# 6_SWITCHING.net
KiCad netlist of a schematic drawn in Altium Designer
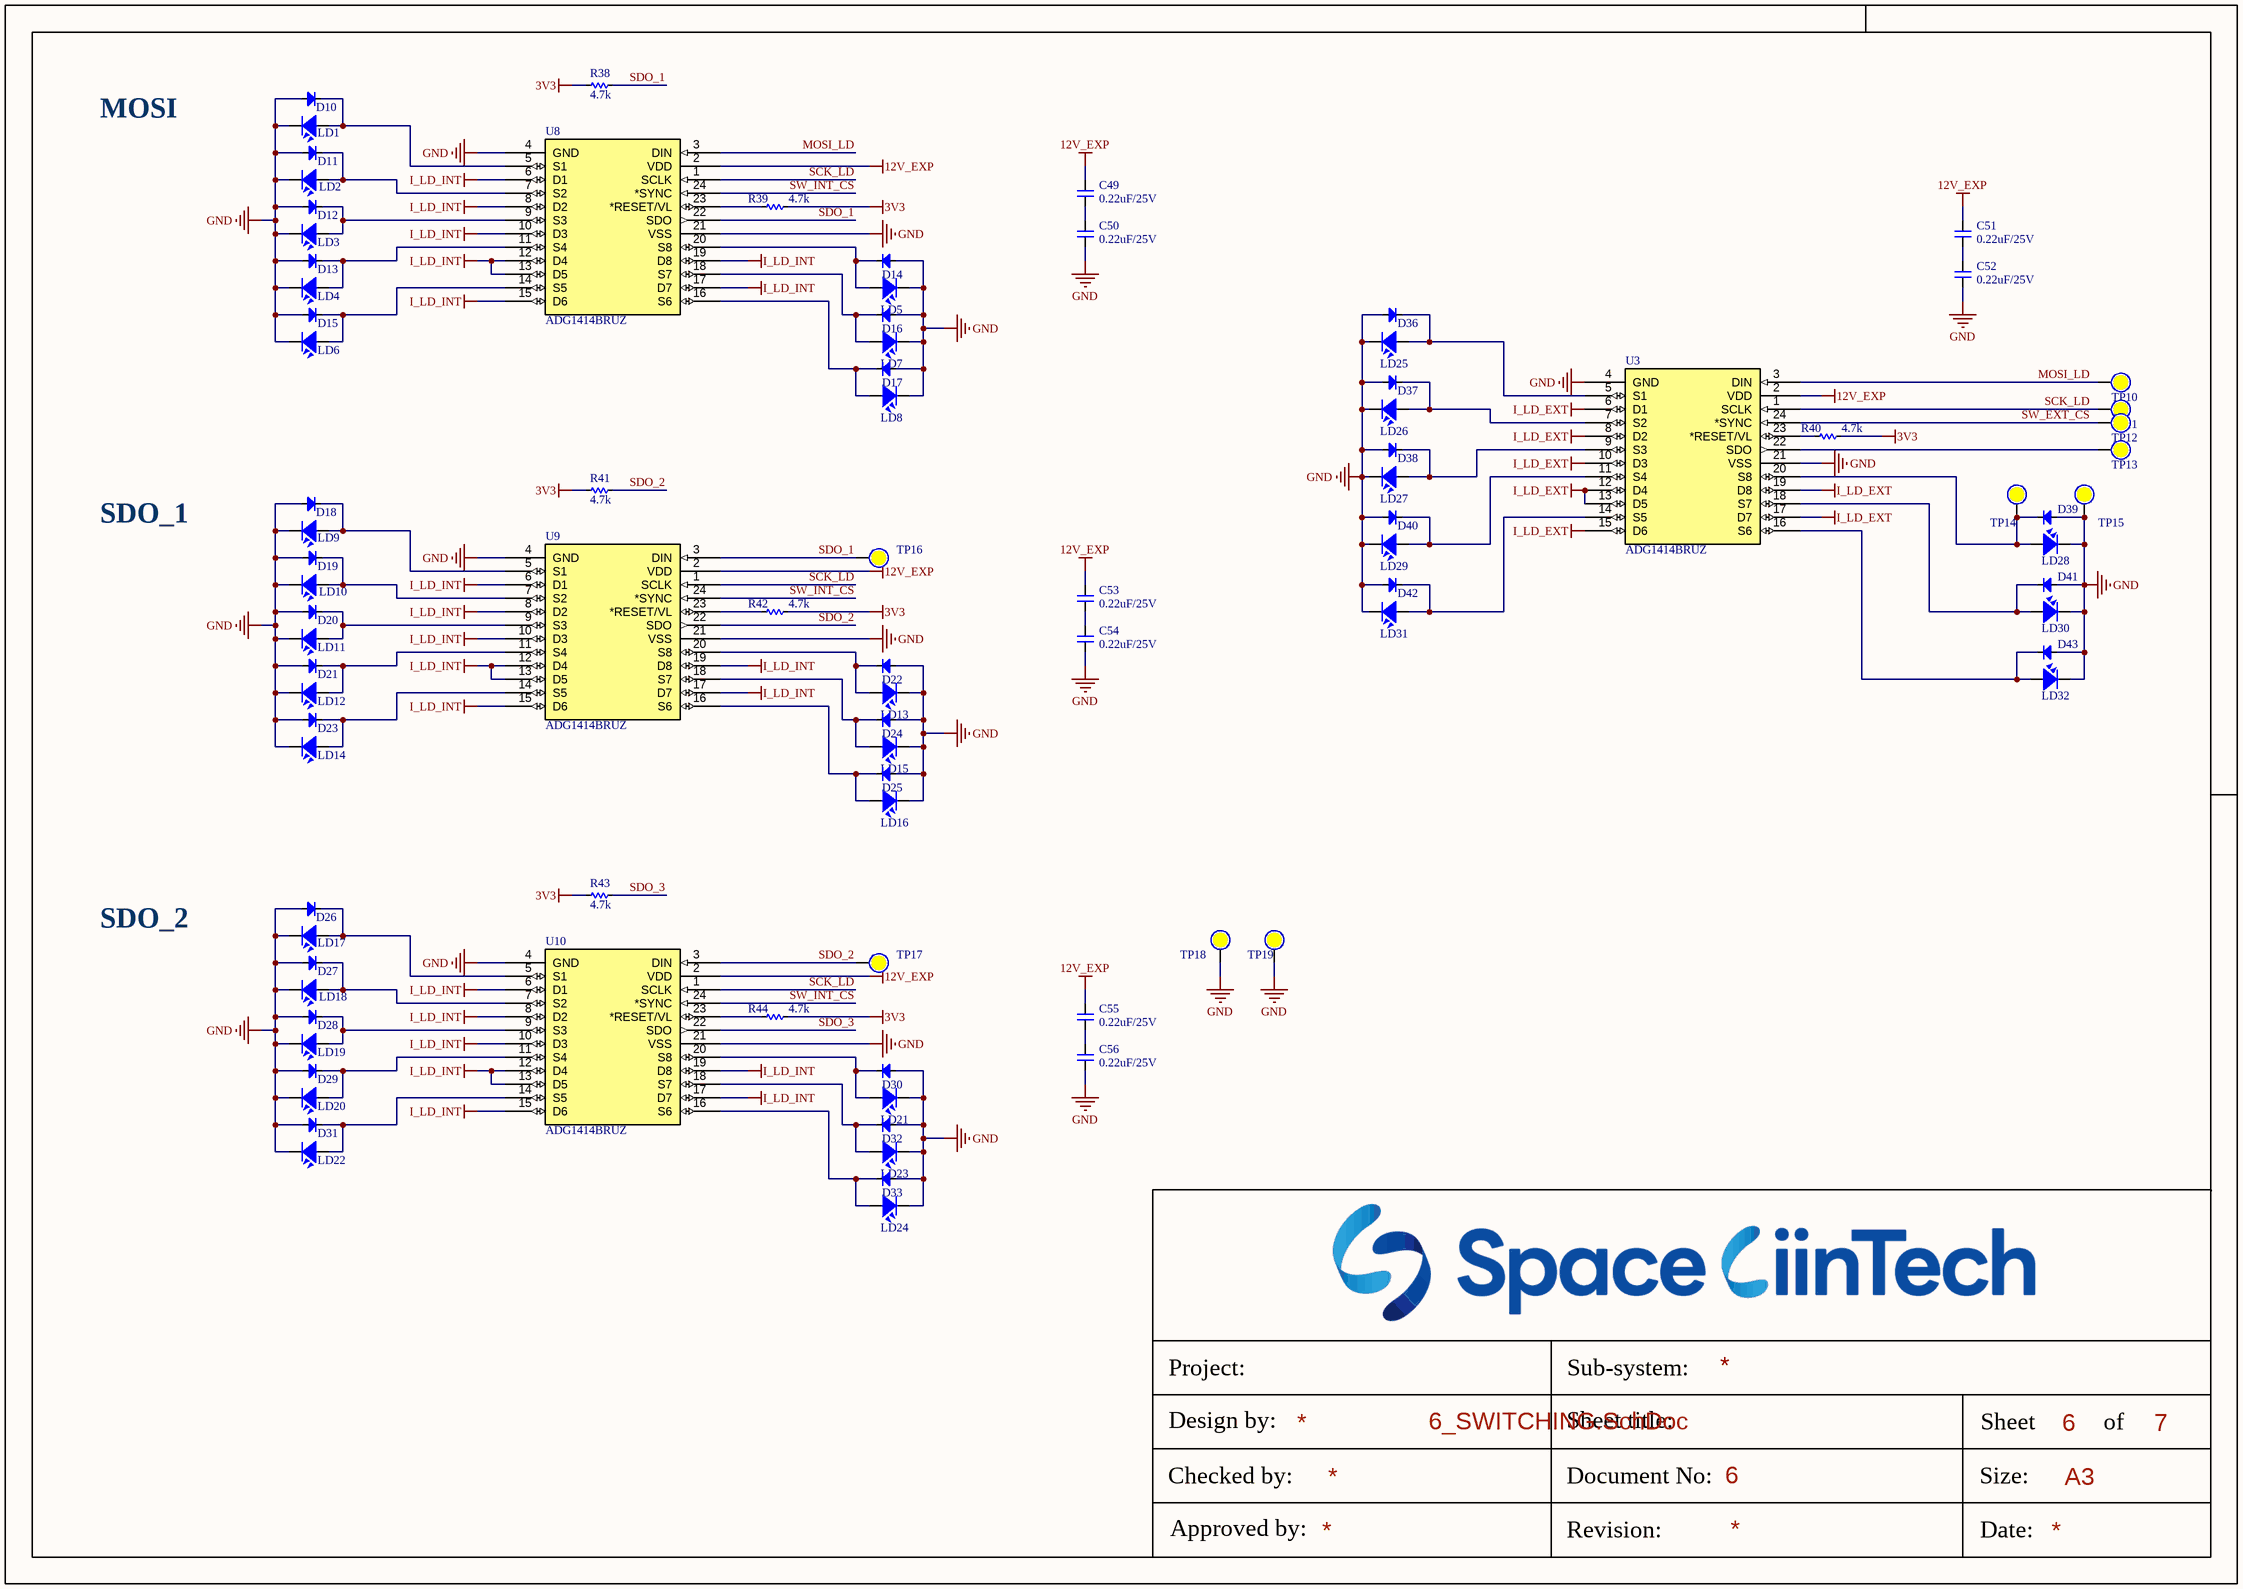
[diagram p0: 6_SWITCHING.SchDoc]

(export (version "E")
  (design (tool "Eeschema 10.0.6"))
  (components
    (comp (ref "C49")
      (value "0.22uF/25V")
      (footprint "CAP_C_1608X80")
      (description "CAP")
      (libsource (lib "LABLIB") (part "_CAP_C_2"))
    )
    (comp (ref "C50")
      (value "0.22uF/25V")
      (footprint "CAP_C_1608X80")
      (description "CAP")
      (libsource (lib "LABLIB") (part "_CAP_C_2"))
    )
    (comp (ref "C51")
      (value "0.22uF/25V")
      (footprint "CAP_C_1608X80")
      (description "CAP")
      (libsource (lib "LABLIB") (part "_CAP_C_2"))
    )
    (comp (ref "C52")
      (value "0.22uF/25V")
      (footprint "CAP_C_1608X80")
      (description "CAP")
      (libsource (lib "LABLIB") (part "_CAP_C_2"))
    )
    (comp (ref "C53")
      (value "0.22uF/25V")
      (footprint "CAP_C_1608X80")
      (description "CAP")
      (libsource (lib "LABLIB") (part "_CAP_C_2"))
    )
    (comp (ref "C54")
      (value "0.22uF/25V")
      (footprint "CAP_C_1608X80")
      (description "CAP")
      (libsource (lib "LABLIB") (part "_CAP_C_2"))
    )
    (comp (ref "C55")
      (value "0.22uF/25V")
      (footprint "CAP_C_1608X80")
      (description "CAP")
      (libsource (lib "LABLIB") (part "_CAP_C_2"))
    )
    (comp (ref "C56")
      (value "0.22uF/25V")
      (footprint "CAP_C_1608X80")
      (description "CAP")
      (libsource (lib "LABLIB") (part "_CAP_C_2"))
    )
    (comp (ref "D10")
      (value "1N4148W-TP")
      (footprint "SOD23")
      (fields (field (name "PUBLISHER") "Altium Limited"))
      (libsource (lib "LASER_LIB_SCHE") (part "Diode SMD"))
    )
    (comp (ref "D11")
      (value "1N4148W-TP")
      (footprint "SOD23")
      (fields (field (name "PUBLISHER") "Altium Limited"))
      (libsource (lib "LASER_LIB_SCHE") (part "Diode SMD"))
    )
    (comp (ref "D12")
      (value "1N4148W-TP")
      (footprint "SOD23")
      (fields (field (name "PUBLISHER") "Altium Limited"))
      (libsource (lib "LASER_LIB_SCHE") (part "Diode SMD"))
    )
    (comp (ref "D13")
      (value "1N4148W-TP")
      (footprint "SOD23")
      (fields (field (name "PUBLISHER") "Altium Limited"))
      (libsource (lib "LASER_LIB_SCHE") (part "Diode SMD"))
    )
    (comp (ref "D14")
      (value "1N4148W-TP")
      (footprint "SOD23")
      (fields (field (name "PUBLISHER") "Altium Limited"))
      (libsource (lib "LASER_LIB_SCHE") (part "Diode SMD"))
    )
    (comp (ref "D15")
      (value "1N4148W-TP")
      (footprint "SOD23")
      (fields (field (name "PUBLISHER") "Altium Limited"))
      (libsource (lib "LASER_LIB_SCHE") (part "Diode SMD"))
    )
    (comp (ref "D16")
      (value "1N4148W-TP")
      (footprint "SOD23")
      (fields (field (name "PUBLISHER") "Altium Limited"))
      (libsource (lib "LASER_LIB_SCHE") (part "Diode SMD"))
    )
    (comp (ref "D17")
      (value "1N4148W-TP")
      (footprint "SOD23")
      (fields (field (name "PUBLISHER") "Altium Limited"))
      (libsource (lib "LASER_LIB_SCHE") (part "Diode SMD"))
    )
    (comp (ref "D18")
      (value "1N4148W-TP")
      (footprint "SOD23")
      (fields (field (name "PUBLISHER") "Altium Limited"))
      (libsource (lib "LASER_LIB_SCHE") (part "Diode SMD"))
    )
    (comp (ref "D19")
      (value "1N4148W-TP")
      (footprint "SOD23")
      (fields (field (name "PUBLISHER") "Altium Limited"))
      (libsource (lib "LASER_LIB_SCHE") (part "Diode SMD"))
    )
    (comp (ref "D20")
      (value "1N4148W-TP")
      (footprint "SOD23")
      (fields (field (name "PUBLISHER") "Altium Limited"))
      (libsource (lib "LASER_LIB_SCHE") (part "Diode SMD"))
    )
    (comp (ref "D21")
      (value "1N4148W-TP")
      (footprint "SOD23")
      (fields (field (name "PUBLISHER") "Altium Limited"))
      (libsource (lib "LASER_LIB_SCHE") (part "Diode SMD"))
    )
    (comp (ref "D22")
      (value "1N4148W-TP")
      (footprint "SOD23")
      (fields (field (name "PUBLISHER") "Altium Limited"))
      (libsource (lib "LASER_LIB_SCHE") (part "Diode SMD"))
    )
    (comp (ref "D23")
      (value "1N4148W-TP")
      (footprint "SOD23")
      (fields (field (name "PUBLISHER") "Altium Limited"))
      (libsource (lib "LASER_LIB_SCHE") (part "Diode SMD"))
    )
    (comp (ref "D24")
      (value "1N4148W-TP")
      (footprint "SOD23")
      (fields (field (name "PUBLISHER") "Altium Limited"))
      (libsource (lib "LASER_LIB_SCHE") (part "Diode SMD"))
    )
    (comp (ref "D25")
      (value "1N4148W-TP")
      (footprint "SOD23")
      (fields (field (name "PUBLISHER") "Altium Limited"))
      (libsource (lib "LASER_LIB_SCHE") (part "Diode SMD"))
    )
    (comp (ref "D26")
      (value "1N4148W-TP")
      (footprint "SOD23")
      (fields (field (name "PUBLISHER") "Altium Limited"))
      (libsource (lib "LASER_LIB_SCHE") (part "Diode SMD"))
    )
    (comp (ref "D27")
      (value "1N4148W-TP")
      (footprint "SOD23")
      (fields (field (name "PUBLISHER") "Altium Limited"))
      (libsource (lib "LASER_LIB_SCHE") (part "Diode SMD"))
    )
    (comp (ref "D28")
      (value "1N4148W-TP")
      (footprint "SOD23")
      (fields (field (name "PUBLISHER") "Altium Limited"))
      (libsource (lib "LASER_LIB_SCHE") (part "Diode SMD"))
    )
    (comp (ref "D29")
      (value "1N4148W-TP")
      (footprint "SOD23")
      (fields (field (name "PUBLISHER") "Altium Limited"))
      (libsource (lib "LASER_LIB_SCHE") (part "Diode SMD"))
    )
    (comp (ref "D30")
      (value "1N4148W-TP")
      (footprint "SOD23")
      (fields (field (name "PUBLISHER") "Altium Limited"))
      (libsource (lib "LASER_LIB_SCHE") (part "Diode SMD"))
    )
    (comp (ref "D31")
      (value "1N4148W-TP")
      (footprint "SOD23")
      (fields (field (name "PUBLISHER") "Altium Limited"))
      (libsource (lib "LASER_LIB_SCHE") (part "Diode SMD"))
    )
    (comp (ref "D32")
      (value "1N4148W-TP")
      (footprint "SOD23")
      (fields (field (name "PUBLISHER") "Altium Limited"))
      (libsource (lib "LASER_LIB_SCHE") (part "Diode SMD"))
    )
    (comp (ref "D33")
      (value "1N4148W-TP")
      (footprint "SOD23")
      (fields (field (name "PUBLISHER") "Altium Limited"))
      (libsource (lib "LASER_LIB_SCHE") (part "Diode SMD"))
    )
    (comp (ref "D36")
      (value "1N4148W-TP")
      (footprint "SOD23")
      (fields (field (name "PUBLISHER") "Altium Limited"))
      (libsource (lib "LASER_LIB_SCHE") (part "Diode SMD"))
    )
    (comp (ref "D37")
      (value "1N4148W-TP")
      (footprint "SOD23")
      (fields (field (name "PUBLISHER") "Altium Limited"))
      (libsource (lib "LASER_LIB_SCHE") (part "Diode SMD"))
    )
    (comp (ref "D38")
      (value "1N4148W-TP")
      (footprint "SOD23")
      (fields (field (name "PUBLISHER") "Altium Limited"))
      (libsource (lib "LASER_LIB_SCHE") (part "Diode SMD"))
    )
    (comp (ref "D39")
      (value "1N4148W-TP")
      (footprint "SOD23")
      (fields (field (name "PUBLISHER") "Altium Limited"))
      (libsource (lib "LASER_LIB_SCHE") (part "Diode SMD"))
    )
    (comp (ref "D40")
      (value "1N4148W-TP")
      (footprint "SOD23")
      (fields (field (name "PUBLISHER") "Altium Limited"))
      (libsource (lib "LASER_LIB_SCHE") (part "Diode SMD"))
    )
    (comp (ref "D41")
      (value "1N4148W-TP")
      (footprint "SOD23")
      (fields (field (name "PUBLISHER") "Altium Limited"))
      (libsource (lib "LASER_LIB_SCHE") (part "Diode SMD"))
    )
    (comp (ref "D42")
      (value "1N4148W-TP")
      (footprint "SOD23")
      (fields (field (name "PUBLISHER") "Altium Limited"))
      (libsource (lib "LASER_LIB_SCHE") (part "Diode SMD"))
    )
    (comp (ref "D43")
      (value "1N4148W-TP")
      (footprint "SOD23")
      (fields (field (name "PUBLISHER") "Altium Limited"))
      (libsource (lib "LASER_LIB_SCHE") (part "Diode SMD"))
    )
    (comp (ref "LD1")
      (value "LaserDiode")
      (footprint "OPV302")
      (description "OPV302")
      (libsource (lib "LASER_LIB_SCHE") (part "LD"))
    )
    (comp (ref "LD2")
      (value "LaserDiode")
      (footprint "OPV302")
      (description "OPV302")
      (libsource (lib "LASER_LIB_SCHE") (part "LD"))
    )
    (comp (ref "LD3")
      (value "LaserDiode")
      (footprint "OPV302")
      (description "OPV302")
      (libsource (lib "LASER_LIB_SCHE") (part "LD"))
    )
    (comp (ref "LD4")
      (value "LaserDiode")
      (footprint "OPV302")
      (description "OPV302")
      (libsource (lib "LASER_LIB_SCHE") (part "LD"))
    )
    (comp (ref "LD5")
      (value "LaserDiode")
      (footprint "OPV302")
      (description "OPV302")
      (libsource (lib "LASER_LIB_SCHE") (part "LD"))
    )
    (comp (ref "LD6")
      (value "LaserDiode")
      (footprint "OPV302")
      (description "OPV302")
      (libsource (lib "LASER_LIB_SCHE") (part "LD"))
    )
    (comp (ref "LD7")
      (value "LaserDiode")
      (footprint "OPV302")
      (description "OPV302")
      (libsource (lib "LASER_LIB_SCHE") (part "LD"))
    )
    (comp (ref "LD8")
      (value "LaserDiode")
      (footprint "OPV302")
      (description "OPV302")
      (libsource (lib "LASER_LIB_SCHE") (part "LD"))
    )
    (comp (ref "LD9")
      (value "LaserDiode")
      (footprint "OPV302")
      (description "OPV302")
      (libsource (lib "LASER_LIB_SCHE") (part "LD"))
    )
    (comp (ref "LD10")
      (value "LaserDiode")
      (footprint "OPV302")
      (description "OPV302")
      (libsource (lib "LASER_LIB_SCHE") (part "LD"))
    )
    (comp (ref "LD11")
      (value "LaserDiode")
      (footprint "OPV302")
      (description "OPV302")
      (libsource (lib "LASER_LIB_SCHE") (part "LD"))
    )
    (comp (ref "LD12")
      (value "LaserDiode")
      (footprint "OPV302")
      (description "OPV302")
      (libsource (lib "LASER_LIB_SCHE") (part "LD"))
    )
    (comp (ref "LD13")
      (value "LaserDiode")
      (footprint "OPV302")
      (description "OPV302")
      (libsource (lib "LASER_LIB_SCHE") (part "LD"))
    )
    (comp (ref "LD14")
      (value "LaserDiode")
      (footprint "OPV302")
      (description "OPV302")
      (libsource (lib "LASER_LIB_SCHE") (part "LD"))
    )
    (comp (ref "LD15")
      (value "LaserDiode")
      (footprint "OPV302")
      (description "OPV302")
      (libsource (lib "LASER_LIB_SCHE") (part "LD"))
    )
    (comp (ref "LD16")
      (value "LaserDiode")
      (footprint "OPV302")
      (description "OPV302")
      (libsource (lib "LASER_LIB_SCHE") (part "LD"))
    )
    (comp (ref "LD17")
      (value "LaserDiode")
      (footprint "OPV302")
      (description "OPV302")
      (libsource (lib "LASER_LIB_SCHE") (part "LD"))
    )
    (comp (ref "LD18")
      (value "LaserDiode")
      (footprint "OPV302")
      (description "OPV302")
      (libsource (lib "LASER_LIB_SCHE") (part "LD"))
    )
    (comp (ref "LD19")
      (value "LaserDiode")
      (footprint "OPV302")
      (description "OPV302")
      (libsource (lib "LASER_LIB_SCHE") (part "LD"))
    )
    (comp (ref "LD20")
      (value "LaserDiode")
      (footprint "OPV302")
      (description "OPV302")
      (libsource (lib "LASER_LIB_SCHE") (part "LD"))
    )
    (comp (ref "LD21")
      (value "LaserDiode")
      (footprint "OPV302")
      (description "OPV302")
      (libsource (lib "LASER_LIB_SCHE") (part "LD"))
    )
    (comp (ref "LD22")
      (value "LaserDiode")
      (footprint "OPV302")
      (description "OPV302")
      (libsource (lib "LASER_LIB_SCHE") (part "LD"))
    )
    (comp (ref "LD23")
      (value "LaserDiode")
      (footprint "OPV302")
      (description "OPV302")
      (libsource (lib "LASER_LIB_SCHE") (part "LD"))
    )
    (comp (ref "LD24")
      (value "LaserDiode")
      (footprint "OPV302")
      (description "OPV302")
      (libsource (lib "LASER_LIB_SCHE") (part "LD"))
    )
    (comp (ref "LD25")
      (value "LaserDiode")
      (footprint "LASER")
      (description "OPV302")
      (libsource (lib "LASER_LIB_SCHE") (part "LD"))
    )
    (comp (ref "LD26")
      (value "LaserDiode")
      (footprint "LASER")
      (description "OPV302")
      (libsource (lib "LASER_LIB_SCHE") (part "LD"))
    )
    (comp (ref "LD27")
      (value "LaserDiode")
      (footprint "LASER")
      (description "OPV302")
      (libsource (lib "LASER_LIB_SCHE") (part "LD"))
    )
    (comp (ref "LD28")
      (value "LaserDiode")
      (footprint "LASER")
      (description "OPV302")
      (libsource (lib "LASER_LIB_SCHE") (part "LD"))
    )
    (comp (ref "LD29")
      (value "LaserDiode")
      (footprint "LASER")
      (description "OPV302")
      (libsource (lib "LASER_LIB_SCHE") (part "LD"))
    )
    (comp (ref "LD30")
      (value "LaserDiode")
      (footprint "LASER")
      (description "OPV302")
      (libsource (lib "LASER_LIB_SCHE") (part "LD"))
    )
    (comp (ref "LD31")
      (value "LaserDiode")
      (footprint "LASER")
      (description "OPV302")
      (libsource (lib "LASER_LIB_SCHE") (part "LD"))
    )
    (comp (ref "LD32")
      (value "LaserDiode")
      (footprint "LASER")
      (description "OPV302")
      (libsource (lib "LASER_LIB_SCHE") (part "LD"))
    )
    (comp (ref "R38")
      (value "4.7k")
      (footprint "RES_C_1608X60")
      (description "RES")
      (libsource (lib "LABLIB") (part "_RES_B_2"))
    )
    (comp (ref "R39")
      (value "4.7k")
      (footprint "RES_C_1608X60")
      (description "RES")
      (libsource (lib "LABLIB") (part "_RES_B_2"))
    )
    (comp (ref "R40")
      (value "4.7k")
      (footprint "RES_C_1608X60")
      (description "RES")
      (libsource (lib "LABLIB") (part "_RES_B_2"))
    )
    (comp (ref "R41")
      (value "4.7k")
      (footprint "RES_C_1608X60")
      (description "RES")
      (libsource (lib "LABLIB") (part "_RES_B_2"))
    )
    (comp (ref "R42")
      (value "4.7k")
      (footprint "RES_C_1608X60")
      (description "RES")
      (libsource (lib "LABLIB") (part "_RES_B_2"))
    )
    (comp (ref "R43")
      (value "4.7k")
      (footprint "RES_C_1608X60")
      (description "RES")
      (libsource (lib "LABLIB") (part "_RES_B_2"))
    )
    (comp (ref "R44")
      (value "4.7k")
      (footprint "RES_C_1608X60")
      (description "RES")
      (libsource (lib "LABLIB") (part "_RES_B_2"))
    )
    (comp (ref "TP10")
      (value "~")
      (footprint "Testpoint_50")
      (description "Test Point")
      (libsource (lib "LASER_LIB_SCHE") (part "Test Point"))
    )
    (comp (ref "TP11")
      (value "~")
      (footprint "Testpoint_50")
      (description "Test Point")
      (libsource (lib "LASER_LIB_SCHE") (part "Test Point"))
    )
    (comp (ref "TP12")
      (value "~")
      (footprint "Testpoint_50")
      (description "Test Point")
      (libsource (lib "LASER_LIB_SCHE") (part "Test Point"))
    )
    (comp (ref "TP13")
      (value "~")
      (footprint "Testpoint_50")
      (description "Test Point")
      (libsource (lib "LASER_LIB_SCHE") (part "Test Point"))
    )
    (comp (ref "TP14")
      (value "~")
      (footprint "Testpoint_50")
      (description "Test Point")
      (libsource (lib "") (part "Test Point_1"))
    )
    (comp (ref "TP15")
      (value "~")
      (footprint "Testpoint_50")
      (description "Test Point")
      (libsource (lib "") (part "Test Point_1"))
    )
    (comp (ref "TP16")
      (value "~")
      (footprint "Testpoint_50")
      (description "Test Point")
      (libsource (lib "LASER_LIB_SCHE") (part "Test Point"))
    )
    (comp (ref "TP17")
      (value "~")
      (footprint "Testpoint_50")
      (description "Test Point")
      (libsource (lib "LASER_LIB_SCHE") (part "Test Point"))
    )
    (comp (ref "TP18")
      (value "~")
      (footprint "Testpoint_50")
      (description "Test Point")
      (libsource (lib "") (part "Test Point_1"))
    )
    (comp (ref "TP19")
      (value "~")
      (footprint "Testpoint_50")
      (description "Test Point")
      (libsource (lib "") (part "Test Point_1"))
    )
    (comp (ref "U3")
      (value "ADG1414BRUZ")
      (footprint "TSSOP24")
      (description "IC SW SPST-NOX8 11.5OHM 24TSSOP")
      (libsource (lib "Library_HUNG") (part "ADG1414BRUZ"))
    )
    (comp (ref "U8")
      (value "ADG1414BRUZ")
      (footprint "TSSOP24")
      (libsource (lib "LASER_LIB_SCHE") (part "ADG1414BRUZ"))
    )
    (comp (ref "U9")
      (value "ADG1414BRUZ")
      (footprint "TSSOP24")
      (libsource (lib "LASER_LIB_SCHE") (part "ADG1414BRUZ"))
    )
    (comp (ref "U10")
      (value "ADG1414BRUZ")
      (footprint "TSSOP24")
      (libsource (lib "LASER_LIB_SCHE") (part "ADG1414BRUZ"))
    )
  )
  (nets
    (net (code "1") (name "/MOSI_LD") (class "Default")
      (node (ref "TP10") (pin "1") (pinfunction "1_1") (pintype "passive"))
      (node (ref "U3") (pin "3") (pinfunction "DIN_3") (pintype "input"))
      (node (ref "U8") (pin "3") (pinfunction "DIN_3") (pintype "input"))
    )
    (net (code "2") (name "/SCK_LD") (class "Default")
      (node (ref "TP11") (pin "1") (pinfunction "1_1") (pintype "passive"))
      (node (ref "U10") (pin "1") (pinfunction "SCLK_1") (pintype "input"))
      (node (ref "U3") (pin "1") (pinfunction "SCLK_1") (pintype "input"))
      (node (ref "U8") (pin "1") (pinfunction "SCLK_1") (pintype "input"))
      (node (ref "U9") (pin "1") (pinfunction "SCLK_1") (pintype "input"))
    )
    (net (code "3") (name "/SDO_1") (class "Default")
      (node (ref "R38") (pin "2") (pinfunction "2_2") (pintype "passive"))
      (node (ref "TP16") (pin "1") (pinfunction "1_1") (pintype "passive"))
      (node (ref "U8") (pin "22") (pinfunction "SDO_22") (pintype "output"))
      (node (ref "U9") (pin "3") (pinfunction "DIN_3") (pintype "input"))
    )
    (net (code "4") (name "/SDO_2") (class "Default")
      (node (ref "R41") (pin "2") (pinfunction "2_2") (pintype "passive"))
      (node (ref "TP17") (pin "1") (pinfunction "1_1") (pintype "passive"))
      (node (ref "U10") (pin "3") (pinfunction "DIN_3") (pintype "input"))
      (node (ref "U9") (pin "22") (pinfunction "SDO_22") (pintype "output"))
    )
    (net (code "5") (name "/SDO_3") (class "Default")
      (node (ref "R43") (pin "2") (pinfunction "2_2") (pintype "passive"))
      (node (ref "U10") (pin "22") (pinfunction "SDO_22") (pintype "output"))
    )
    (net (code "6") (name "/SW_EXT_CS") (class "Default")
      (node (ref "TP12") (pin "1") (pinfunction "1_1") (pintype "passive"))
      (node (ref "U3") (pin "24") (pinfunction "*SYNC_24") (pintype "input"))
    )
    (net (code "7") (name "/SW_INT_CS") (class "Default")
      (node (ref "U10") (pin "24") (pinfunction "*SYNC_24") (pintype "input"))
      (node (ref "U8") (pin "24") (pinfunction "*SYNC_24") (pintype "input"))
      (node (ref "U9") (pin "24") (pinfunction "*SYNC_24") (pintype "input"))
    )
    (net (code "8") (name "3V3") (class "Default")
      (node (ref "R38") (pin "1") (pinfunction "1_1") (pintype "passive"))
      (node (ref "R39") (pin "2") (pinfunction "2_2") (pintype "passive"))
      (node (ref "R40") (pin "2") (pinfunction "2_2") (pintype "passive"))
      (node (ref "R41") (pin "1") (pinfunction "1_1") (pintype "passive"))
      (node (ref "R42") (pin "2") (pinfunction "2_2") (pintype "passive"))
      (node (ref "R43") (pin "1") (pinfunction "1_1") (pintype "passive"))
      (node (ref "R44") (pin "2") (pinfunction "2_2") (pintype "passive"))
    )
    (net (code "9") (name "12V_EXP") (class "Default")
      (node (ref "C49") (pin "2") (pinfunction "2_2") (pintype "passive"))
      (node (ref "C51") (pin "2") (pinfunction "2_2") (pintype "passive"))
      (node (ref "C53") (pin "2") (pinfunction "2_2") (pintype "passive"))
      (node (ref "C55") (pin "2") (pinfunction "2_2") (pintype "passive"))
      (node (ref "U10") (pin "2") (pinfunction "VDD_2") (pintype "power_in"))
      (node (ref "U3") (pin "2") (pinfunction "VDD_2") (pintype "power_in"))
      (node (ref "U8") (pin "2") (pinfunction "VDD_2") (pintype "power_in"))
      (node (ref "U9") (pin "2") (pinfunction "VDD_2") (pintype "power_in"))
    )
    (net (code "10") (name "GND") (class "Default")
      (node (ref "C50") (pin "1") (pinfunction "1_1") (pintype "passive"))
      (node (ref "C52") (pin "1") (pinfunction "1_1") (pintype "passive"))
      (node (ref "C54") (pin "1") (pinfunction "1_1") (pintype "passive"))
      (node (ref "C56") (pin "1") (pinfunction "1_1") (pintype "passive"))
      (node (ref "D10") (pin "1") (pinfunction "A_1") (pintype "passive"))
      (node (ref "D11") (pin "1") (pinfunction "A_1") (pintype "passive"))
      (node (ref "D12") (pin "1") (pinfunction "A_1") (pintype "passive"))
      (node (ref "D13") (pin "1") (pinfunction "A_1") (pintype "passive"))
      (node (ref "D14") (pin "1") (pinfunction "A_1") (pintype "passive"))
      (node (ref "D15") (pin "1") (pinfunction "A_1") (pintype "passive"))
      (node (ref "D16") (pin "1") (pinfunction "A_1") (pintype "passive"))
      (node (ref "D17") (pin "1") (pinfunction "A_1") (pintype "passive"))
      (node (ref "D18") (pin "1") (pinfunction "A_1") (pintype "passive"))
      (node (ref "D19") (pin "1") (pinfunction "A_1") (pintype "passive"))
      (node (ref "D20") (pin "1") (pinfunction "A_1") (pintype "passive"))
      (node (ref "D21") (pin "1") (pinfunction "A_1") (pintype "passive"))
      (node (ref "D22") (pin "1") (pinfunction "A_1") (pintype "passive"))
      (node (ref "D23") (pin "1") (pinfunction "A_1") (pintype "passive"))
      (node (ref "D24") (pin "1") (pinfunction "A_1") (pintype "passive"))
      (node (ref "D25") (pin "1") (pinfunction "A_1") (pintype "passive"))
      (node (ref "D26") (pin "1") (pinfunction "A_1") (pintype "passive"))
      (node (ref "D27") (pin "1") (pinfunction "A_1") (pintype "passive"))
      (node (ref "D28") (pin "1") (pinfunction "A_1") (pintype "passive"))
      (node (ref "D29") (pin "1") (pinfunction "A_1") (pintype "passive"))
      (node (ref "D30") (pin "1") (pinfunction "A_1") (pintype "passive"))
      (node (ref "D31") (pin "1") (pinfunction "A_1") (pintype "passive"))
      (node (ref "D32") (pin "1") (pinfunction "A_1") (pintype "passive"))
      (node (ref "D33") (pin "1") (pinfunction "A_1") (pintype "passive"))
      (node (ref "D36") (pin "1") (pinfunction "A_1") (pintype "passive"))
      (node (ref "D37") (pin "1") (pinfunction "A_1") (pintype "passive"))
      (node (ref "D38") (pin "1") (pinfunction "A_1") (pintype "passive"))
      (node (ref "D39") (pin "1") (pinfunction "A_1") (pintype "passive"))
      (node (ref "D40") (pin "1") (pinfunction "A_1") (pintype "passive"))
      (node (ref "D41") (pin "1") (pinfunction "A_1") (pintype "passive"))
      (node (ref "D42") (pin "1") (pinfunction "A_1") (pintype "passive"))
      (node (ref "D43") (pin "1") (pinfunction "A_1") (pintype "passive"))
      (node (ref "LD1") (pin "3") (pinfunction "3_3") (pintype "passive"))
      (node (ref "LD10") (pin "3") (pinfunction "3_3") (pintype "passive"))
      (node (ref "LD11") (pin "3") (pinfunction "3_3") (pintype "passive"))
      (node (ref "LD12") (pin "3") (pinfunction "3_3") (pintype "passive"))
      (node (ref "LD13") (pin "3") (pinfunction "3_3") (pintype "passive"))
      (node (ref "LD14") (pin "3") (pinfunction "3_3") (pintype "passive"))
      (node (ref "LD15") (pin "3") (pinfunction "3_3") (pintype "passive"))
      (node (ref "LD16") (pin "3") (pinfunction "3_3") (pintype "passive"))
      (node (ref "LD17") (pin "3") (pinfunction "3_3") (pintype "passive"))
      (node (ref "LD18") (pin "3") (pinfunction "3_3") (pintype "passive"))
      (node (ref "LD19") (pin "3") (pinfunction "3_3") (pintype "passive"))
      (node (ref "LD2") (pin "3") (pinfunction "3_3") (pintype "passive"))
      (node (ref "LD20") (pin "3") (pinfunction "3_3") (pintype "passive"))
      (node (ref "LD21") (pin "3") (pinfunction "3_3") (pintype "passive"))
      (node (ref "LD22") (pin "3") (pinfunction "3_3") (pintype "passive"))
      (node (ref "LD23") (pin "3") (pinfunction "3_3") (pintype "passive"))
      (node (ref "LD24") (pin "3") (pinfunction "3_3") (pintype "passive"))
      (node (ref "LD25") (pin "3") (pinfunction "3_3") (pintype "passive"))
      (node (ref "LD26") (pin "3") (pinfunction "3_3") (pintype "passive"))
      (node (ref "LD27") (pin "3") (pinfunction "3_3") (pintype "passive"))
      (node (ref "LD28") (pin "3") (pinfunction "3_3") (pintype "passive"))
      (node (ref "LD29") (pin "3") (pinfunction "3_3") (pintype "passive"))
      (node (ref "LD3") (pin "3") (pinfunction "3_3") (pintype "passive"))
      (node (ref "LD30") (pin "3") (pinfunction "3_3") (pintype "passive"))
      (node (ref "LD31") (pin "3") (pinfunction "3_3") (pintype "passive"))
      (node (ref "LD32") (pin "3") (pinfunction "3_3") (pintype "passive"))
      (node (ref "LD4") (pin "3") (pinfunction "3_3") (pintype "passive"))
      (node (ref "LD5") (pin "3") (pinfunction "3_3") (pintype "passive"))
      (node (ref "LD6") (pin "3") (pinfunction "3_3") (pintype "passive"))
      (node (ref "LD7") (pin "3") (pinfunction "3_3") (pintype "passive"))
      (node (ref "LD8") (pin "3") (pinfunction "3_3") (pintype "passive"))
      (node (ref "LD9") (pin "3") (pinfunction "3_3") (pintype "passive"))
      (node (ref "TP15") (pin "1") (pinfunction "1_1") (pintype "passive"))
      (node (ref "TP18") (pin "1") (pinfunction "1_1") (pintype "passive"))
      (node (ref "TP19") (pin "1") (pinfunction "1_1") (pintype "passive"))
      (node (ref "U10") (pin "21") (pinfunction "VSS_21") (pintype "power_in"))
      (node (ref "U10") (pin "4") (pinfunction "GND_4") (pintype "power_in"))
      (node (ref "U3") (pin "21") (pinfunction "VSS_21") (pintype "power_in"))
      (node (ref "U3") (pin "4") (pinfunction "GND_4") (pintype "power_in"))
      (node (ref "U8") (pin "21") (pinfunction "VSS_21") (pintype "power_in"))
      (node (ref "U8") (pin "4") (pinfunction "GND_4") (pintype "power_in"))
      (node (ref "U9") (pin "21") (pinfunction "VSS_21") (pintype "power_in"))
      (node (ref "U9") (pin "4") (pinfunction "GND_4") (pintype "power_in"))
    )
    (net (code "11") (name "I_LD_EXT") (class "Default")
      (node (ref "U3") (pin "10") (pinfunction "D3_10") (pintype "bidirectional"))
      (node (ref "U3") (pin "12") (pinfunction "D4_12") (pintype "bidirectional"))
      (node (ref "U3") (pin "13") (pinfunction "D5_13") (pintype "bidirectional"))
      (node (ref "U3") (pin "15") (pinfunction "D6_15") (pintype "bidirectional"))
      (node (ref "U3") (pin "17") (pinfunction "D7_17") (pintype "bidirectional"))
      (node (ref "U3") (pin "19") (pinfunction "D8_19") (pintype "bidirectional"))
      (node (ref "U3") (pin "6") (pinfunction "D1_6") (pintype "bidirectional"))
      (node (ref "U3") (pin "8") (pinfunction "D2_8") (pintype "bidirectional"))
    )
    (net (code "12") (name "I_LD_INT") (class "Default")
      (node (ref "U10") (pin "10") (pinfunction "D3_10") (pintype "bidirectional"))
      (node (ref "U10") (pin "12") (pinfunction "D4_12") (pintype "bidirectional"))
      (node (ref "U10") (pin "13") (pinfunction "D5_13") (pintype "bidirectional"))
      (node (ref "U10") (pin "15") (pinfunction "D6_15") (pintype "bidirectional"))
      (node (ref "U10") (pin "17") (pinfunction "D7_17") (pintype "bidirectional"))
      (node (ref "U10") (pin "19") (pinfunction "D8_19") (pintype "bidirectional"))
      (node (ref "U10") (pin "6") (pinfunction "D1_6") (pintype "bidirectional"))
      (node (ref "U10") (pin "8") (pinfunction "D2_8") (pintype "bidirectional"))
      (node (ref "U8") (pin "10") (pinfunction "D3_10") (pintype "bidirectional"))
      (node (ref "U8") (pin "12") (pinfunction "D4_12") (pintype "bidirectional"))
      (node (ref "U8") (pin "13") (pinfunction "D5_13") (pintype "bidirectional"))
      (node (ref "U8") (pin "15") (pinfunction "D6_15") (pintype "bidirectional"))
      (node (ref "U8") (pin "17") (pinfunction "D7_17") (pintype "bidirectional"))
      (node (ref "U8") (pin "19") (pinfunction "D8_19") (pintype "bidirectional"))
      (node (ref "U8") (pin "6") (pinfunction "D1_6") (pintype "bidirectional"))
      (node (ref "U8") (pin "8") (pinfunction "D2_8") (pintype "bidirectional"))
      (node (ref "U9") (pin "10") (pinfunction "D3_10") (pintype "bidirectional"))
      (node (ref "U9") (pin "12") (pinfunction "D4_12") (pintype "bidirectional"))
      (node (ref "U9") (pin "13") (pinfunction "D5_13") (pintype "bidirectional"))
      (node (ref "U9") (pin "15") (pinfunction "D6_15") (pintype "bidirectional"))
      (node (ref "U9") (pin "17") (pinfunction "D7_17") (pintype "bidirectional"))
      (node (ref "U9") (pin "19") (pinfunction "D8_19") (pintype "bidirectional"))
      (node (ref "U9") (pin "6") (pinfunction "D1_6") (pintype "bidirectional"))
      (node (ref "U9") (pin "8") (pinfunction "D2_8") (pintype "bidirectional"))
    )
    (net (code "13") (name "Net-(C49-Pad1)") (class "Default")
      (node (ref "C49") (pin "1") (pinfunction "1_1") (pintype "passive"))
      (node (ref "C50") (pin "2") (pinfunction "2_2") (pintype "passive"))
    )
    (net (code "14") (name "Net-(C51-Pad1)") (class "Default")
      (node (ref "C51") (pin "1") (pinfunction "1_1") (pintype "passive"))
      (node (ref "C52") (pin "2") (pinfunction "2_2") (pintype "passive"))
    )
    (net (code "15") (name "Net-(C53-Pad1)") (class "Default")
      (node (ref "C53") (pin "1") (pinfunction "1_1") (pintype "passive"))
      (node (ref "C54") (pin "2") (pinfunction "2_2") (pintype "passive"))
    )
    (net (code "16") (name "Net-(C55-Pad1)") (class "Default")
      (node (ref "C55") (pin "1") (pinfunction "1_1") (pintype "passive"))
      (node (ref "C56") (pin "2") (pinfunction "2_2") (pintype "passive"))
    )
    (net (code "17") (name "Net-(D10-K)") (class "Default")
      (node (ref "D10") (pin "2") (pinfunction "K_2") (pintype "passive"))
      (node (ref "LD1") (pin "1") (pinfunction "1_1") (pintype "passive"))
      (node (ref "U8") (pin "5") (pinfunction "S1_5") (pintype "bidirectional"))
    )
    (net (code "18") (name "Net-(D11-K)") (class "Default")
      (node (ref "D11") (pin "2") (pinfunction "K_2") (pintype "passive"))
      (node (ref "LD2") (pin "1") (pinfunction "1_1") (pintype "passive"))
      (node (ref "U8") (pin "7") (pinfunction "S2_7") (pintype "bidirectional"))
    )
    (net (code "19") (name "Net-(D12-K)") (class "Default")
      (node (ref "D12") (pin "2") (pinfunction "K_2") (pintype "passive"))
      (node (ref "LD3") (pin "1") (pinfunction "1_1") (pintype "passive"))
      (node (ref "U8") (pin "9") (pinfunction "S3_9") (pintype "bidirectional"))
    )
    (net (code "20") (name "Net-(D13-K)") (class "Default")
      (node (ref "D13") (pin "2") (pinfunction "K_2") (pintype "passive"))
      (node (ref "LD4") (pin "1") (pinfunction "1_1") (pintype "passive"))
      (node (ref "U8") (pin "11") (pinfunction "S4_11") (pintype "bidirectional"))
    )
    (net (code "21") (name "Net-(D14-K)") (class "Default")
      (node (ref "D14") (pin "2") (pinfunction "K_2") (pintype "passive"))
      (node (ref "LD5") (pin "1") (pinfunction "1_1") (pintype "passive"))
      (node (ref "U8") (pin "20") (pinfunction "S8_20") (pintype "bidirectional"))
    )
    (net (code "22") (name "Net-(D15-K)") (class "Default")
      (node (ref "D15") (pin "2") (pinfunction "K_2") (pintype "passive"))
      (node (ref "LD6") (pin "1") (pinfunction "1_1") (pintype "passive"))
      (node (ref "U8") (pin "14") (pinfunction "S5_14") (pintype "bidirectional"))
    )
    (net (code "23") (name "Net-(D16-K)") (class "Default")
      (node (ref "D16") (pin "2") (pinfunction "K_2") (pintype "passive"))
      (node (ref "LD7") (pin "1") (pinfunction "1_1") (pintype "passive"))
      (node (ref "U8") (pin "18") (pinfunction "S7_18") (pintype "bidirectional"))
    )
    (net (code "24") (name "Net-(D17-K)") (class "Default")
      (node (ref "D17") (pin "2") (pinfunction "K_2") (pintype "passive"))
      (node (ref "LD8") (pin "1") (pinfunction "1_1") (pintype "passive"))
      (node (ref "U8") (pin "16") (pinfunction "S6_16") (pintype "bidirectional"))
    )
    (net (code "25") (name "Net-(D18-K)") (class "Default")
      (node (ref "D18") (pin "2") (pinfunction "K_2") (pintype "passive"))
      (node (ref "LD9") (pin "1") (pinfunction "1_1") (pintype "passive"))
      (node (ref "U9") (pin "5") (pinfunction "S1_5") (pintype "bidirectional"))
    )
    (net (code "26") (name "Net-(D19-K)") (class "Default")
      (node (ref "D19") (pin "2") (pinfunction "K_2") (pintype "passive"))
      (node (ref "LD10") (pin "1") (pinfunction "1_1") (pintype "passive"))
      (node (ref "U9") (pin "7") (pinfunction "S2_7") (pintype "bidirectional"))
    )
    (net (code "27") (name "Net-(D20-K)") (class "Default")
      (node (ref "D20") (pin "2") (pinfunction "K_2") (pintype "passive"))
      (node (ref "LD11") (pin "1") (pinfunction "1_1") (pintype "passive"))
      (node (ref "U9") (pin "9") (pinfunction "S3_9") (pintype "bidirectional"))
    )
    (net (code "28") (name "Net-(D21-K)") (class "Default")
      (node (ref "D21") (pin "2") (pinfunction "K_2") (pintype "passive"))
      (node (ref "LD12") (pin "1") (pinfunction "1_1") (pintype "passive"))
      (node (ref "U9") (pin "11") (pinfunction "S4_11") (pintype "bidirectional"))
    )
    (net (code "29") (name "Net-(D22-K)") (class "Default")
      (node (ref "D22") (pin "2") (pinfunction "K_2") (pintype "passive"))
      (node (ref "LD13") (pin "1") (pinfunction "1_1") (pintype "passive"))
      (node (ref "U9") (pin "20") (pinfunction "S8_20") (pintype "bidirectional"))
    )
    (net (code "30") (name "Net-(D23-K)") (class "Default")
      (node (ref "D23") (pin "2") (pinfunction "K_2") (pintype "passive"))
      (node (ref "LD14") (pin "1") (pinfunction "1_1") (pintype "passive"))
      (node (ref "U9") (pin "14") (pinfunction "S5_14") (pintype "bidirectional"))
    )
    (net (code "31") (name "Net-(D24-K)") (class "Default")
      (node (ref "D24") (pin "2") (pinfunction "K_2") (pintype "passive"))
      (node (ref "LD15") (pin "1") (pinfunction "1_1") (pintype "passive"))
      (node (ref "U9") (pin "18") (pinfunction "S7_18") (pintype "bidirectional"))
    )
    (net (code "32") (name "Net-(D25-K)") (class "Default")
      (node (ref "D25") (pin "2") (pinfunction "K_2") (pintype "passive"))
      (node (ref "LD16") (pin "1") (pinfunction "1_1") (pintype "passive"))
      (node (ref "U9") (pin "16") (pinfunction "S6_16") (pintype "bidirectional"))
    )
    (net (code "33") (name "Net-(D26-K)") (class "Default")
      (node (ref "D26") (pin "2") (pinfunction "K_2") (pintype "passive"))
      (node (ref "LD17") (pin "1") (pinfunction "1_1") (pintype "passive"))
      (node (ref "U10") (pin "5") (pinfunction "S1_5") (pintype "bidirectional"))
    )
    (net (code "34") (name "Net-(D27-K)") (class "Default")
      (node (ref "D27") (pin "2") (pinfunction "K_2") (pintype "passive"))
      (node (ref "LD18") (pin "1") (pinfunction "1_1") (pintype "passive"))
      (node (ref "U10") (pin "7") (pinfunction "S2_7") (pintype "bidirectional"))
    )
    (net (code "35") (name "Net-(D28-K)") (class "Default")
      (node (ref "D28") (pin "2") (pinfunction "K_2") (pintype "passive"))
      (node (ref "LD19") (pin "1") (pinfunction "1_1") (pintype "passive"))
      (node (ref "U10") (pin "9") (pinfunction "S3_9") (pintype "bidirectional"))
    )
    (net (code "36") (name "Net-(D29-K)") (class "Default")
      (node (ref "D29") (pin "2") (pinfunction "K_2") (pintype "passive"))
      (node (ref "LD20") (pin "1") (pinfunction "1_1") (pintype "passive"))
      (node (ref "U10") (pin "11") (pinfunction "S4_11") (pintype "bidirectional"))
    )
    (net (code "37") (name "Net-(D30-K)") (class "Default")
      (node (ref "D30") (pin "2") (pinfunction "K_2") (pintype "passive"))
      (node (ref "LD21") (pin "1") (pinfunction "1_1") (pintype "passive"))
      (node (ref "U10") (pin "20") (pinfunction "S8_20") (pintype "bidirectional"))
    )
    (net (code "38") (name "Net-(D31-K)") (class "Default")
      (node (ref "D31") (pin "2") (pinfunction "K_2") (pintype "passive"))
      (node (ref "LD22") (pin "1") (pinfunction "1_1") (pintype "passive"))
      (node (ref "U10") (pin "14") (pinfunction "S5_14") (pintype "bidirectional"))
    )
    (net (code "39") (name "Net-(D32-K)") (class "Default")
      (node (ref "D32") (pin "2") (pinfunction "K_2") (pintype "passive"))
      (node (ref "LD23") (pin "1") (pinfunction "1_1") (pintype "passive"))
      (node (ref "U10") (pin "18") (pinfunction "S7_18") (pintype "bidirectional"))
    )
    (net (code "40") (name "Net-(D33-K)") (class "Default")
      (node (ref "D33") (pin "2") (pinfunction "K_2") (pintype "passive"))
      (node (ref "LD24") (pin "1") (pinfunction "1_1") (pintype "passive"))
      (node (ref "U10") (pin "16") (pinfunction "S6_16") (pintype "bidirectional"))
    )
    (net (code "41") (name "Net-(D36-K)") (class "Default")
      (node (ref "D36") (pin "2") (pinfunction "K_2") (pintype "passive"))
      (node (ref "LD25") (pin "1") (pinfunction "1_1") (pintype "passive"))
      (node (ref "U3") (pin "5") (pinfunction "S1_5") (pintype "bidirectional"))
    )
    (net (code "42") (name "Net-(D37-K)") (class "Default")
      (node (ref "D37") (pin "2") (pinfunction "K_2") (pintype "passive"))
      (node (ref "LD26") (pin "1") (pinfunction "1_1") (pintype "passive"))
      (node (ref "U3") (pin "7") (pinfunction "S2_7") (pintype "bidirectional"))
    )
    (net (code "43") (name "Net-(D38-K)") (class "Default")
      (node (ref "D38") (pin "2") (pinfunction "K_2") (pintype "passive"))
      (node (ref "LD27") (pin "1") (pinfunction "1_1") (pintype "passive"))
      (node (ref "U3") (pin "9") (pinfunction "S3_9") (pintype "bidirectional"))
    )
    (net (code "44") (name "Net-(D39-K)") (class "Default")
      (node (ref "D39") (pin "2") (pinfunction "K_2") (pintype "passive"))
      (node (ref "LD28") (pin "1") (pinfunction "1_1") (pintype "passive"))
      (node (ref "TP14") (pin "1") (pinfunction "1_1") (pintype "passive"))
      (node (ref "U3") (pin "20") (pinfunction "S8_20") (pintype "bidirectional"))
    )
    (net (code "45") (name "Net-(D40-K)") (class "Default")
      (node (ref "D40") (pin "2") (pinfunction "K_2") (pintype "passive"))
      (node (ref "LD29") (pin "1") (pinfunction "1_1") (pintype "passive"))
      (node (ref "U3") (pin "11") (pinfunction "S4_11") (pintype "bidirectional"))
    )
    (net (code "46") (name "Net-(D41-K)") (class "Default")
      (node (ref "D41") (pin "2") (pinfunction "K_2") (pintype "passive"))
      (node (ref "LD30") (pin "1") (pinfunction "1_1") (pintype "passive"))
      (node (ref "U3") (pin "18") (pinfunction "S7_18") (pintype "bidirectional"))
    )
    (net (code "47") (name "Net-(D42-K)") (class "Default")
      (node (ref "D42") (pin "2") (pinfunction "K_2") (pintype "passive"))
      (node (ref "LD31") (pin "1") (pinfunction "1_1") (pintype "passive"))
      (node (ref "U3") (pin "14") (pinfunction "S5_14") (pintype "bidirectional"))
    )
    (net (code "48") (name "Net-(D43-K)") (class "Default")
      (node (ref "D43") (pin "2") (pinfunction "K_2") (pintype "passive"))
      (node (ref "LD32") (pin "1") (pinfunction "1_1") (pintype "passive"))
      (node (ref "U3") (pin "16") (pinfunction "S6_16") (pintype "bidirectional"))
    )
    (net (code "49") (name "Net-(U3-*RESET{slash}VL)") (class "Default")
      (node (ref "R40") (pin "1") (pinfunction "1_1") (pintype "passive"))
      (node (ref "U3") (pin "23") (pinfunction "*RESET/VL_23") (pintype "bidirectional"))
    )
    (net (code "50") (name "Net-(U3-SDO)") (class "Default")
      (node (ref "TP13") (pin "1") (pinfunction "1_1") (pintype "passive"))
      (node (ref "U3") (pin "22") (pinfunction "SDO_22") (pintype "output"))
    )
    (net (code "51") (name "Net-(U8-*RESET{slash}VL)") (class "Default")
      (node (ref "R39") (pin "1") (pinfunction "1_1") (pintype "passive"))
      (node (ref "U8") (pin "23") (pinfunction "*RESET/VL_23") (pintype "bidirectional"))
    )
    (net (code "52") (name "Net-(U9-*RESET{slash}VL)") (class "Default")
      (node (ref "R42") (pin "1") (pinfunction "1_1") (pintype "passive"))
      (node (ref "U9") (pin "23") (pinfunction "*RESET/VL_23") (pintype "bidirectional"))
    )
    (net (code "53") (name "Net-(U10-*RESET{slash}VL)") (class "Default")
      (node (ref "R44") (pin "1") (pinfunction "1_1") (pintype "passive"))
      (node (ref "U10") (pin "23") (pinfunction "*RESET/VL_23") (pintype "bidirectional"))
    )
  )
)
